# Aquarium_Schematic.net
KiCad netlist of a schematic drawn in EasyEDA
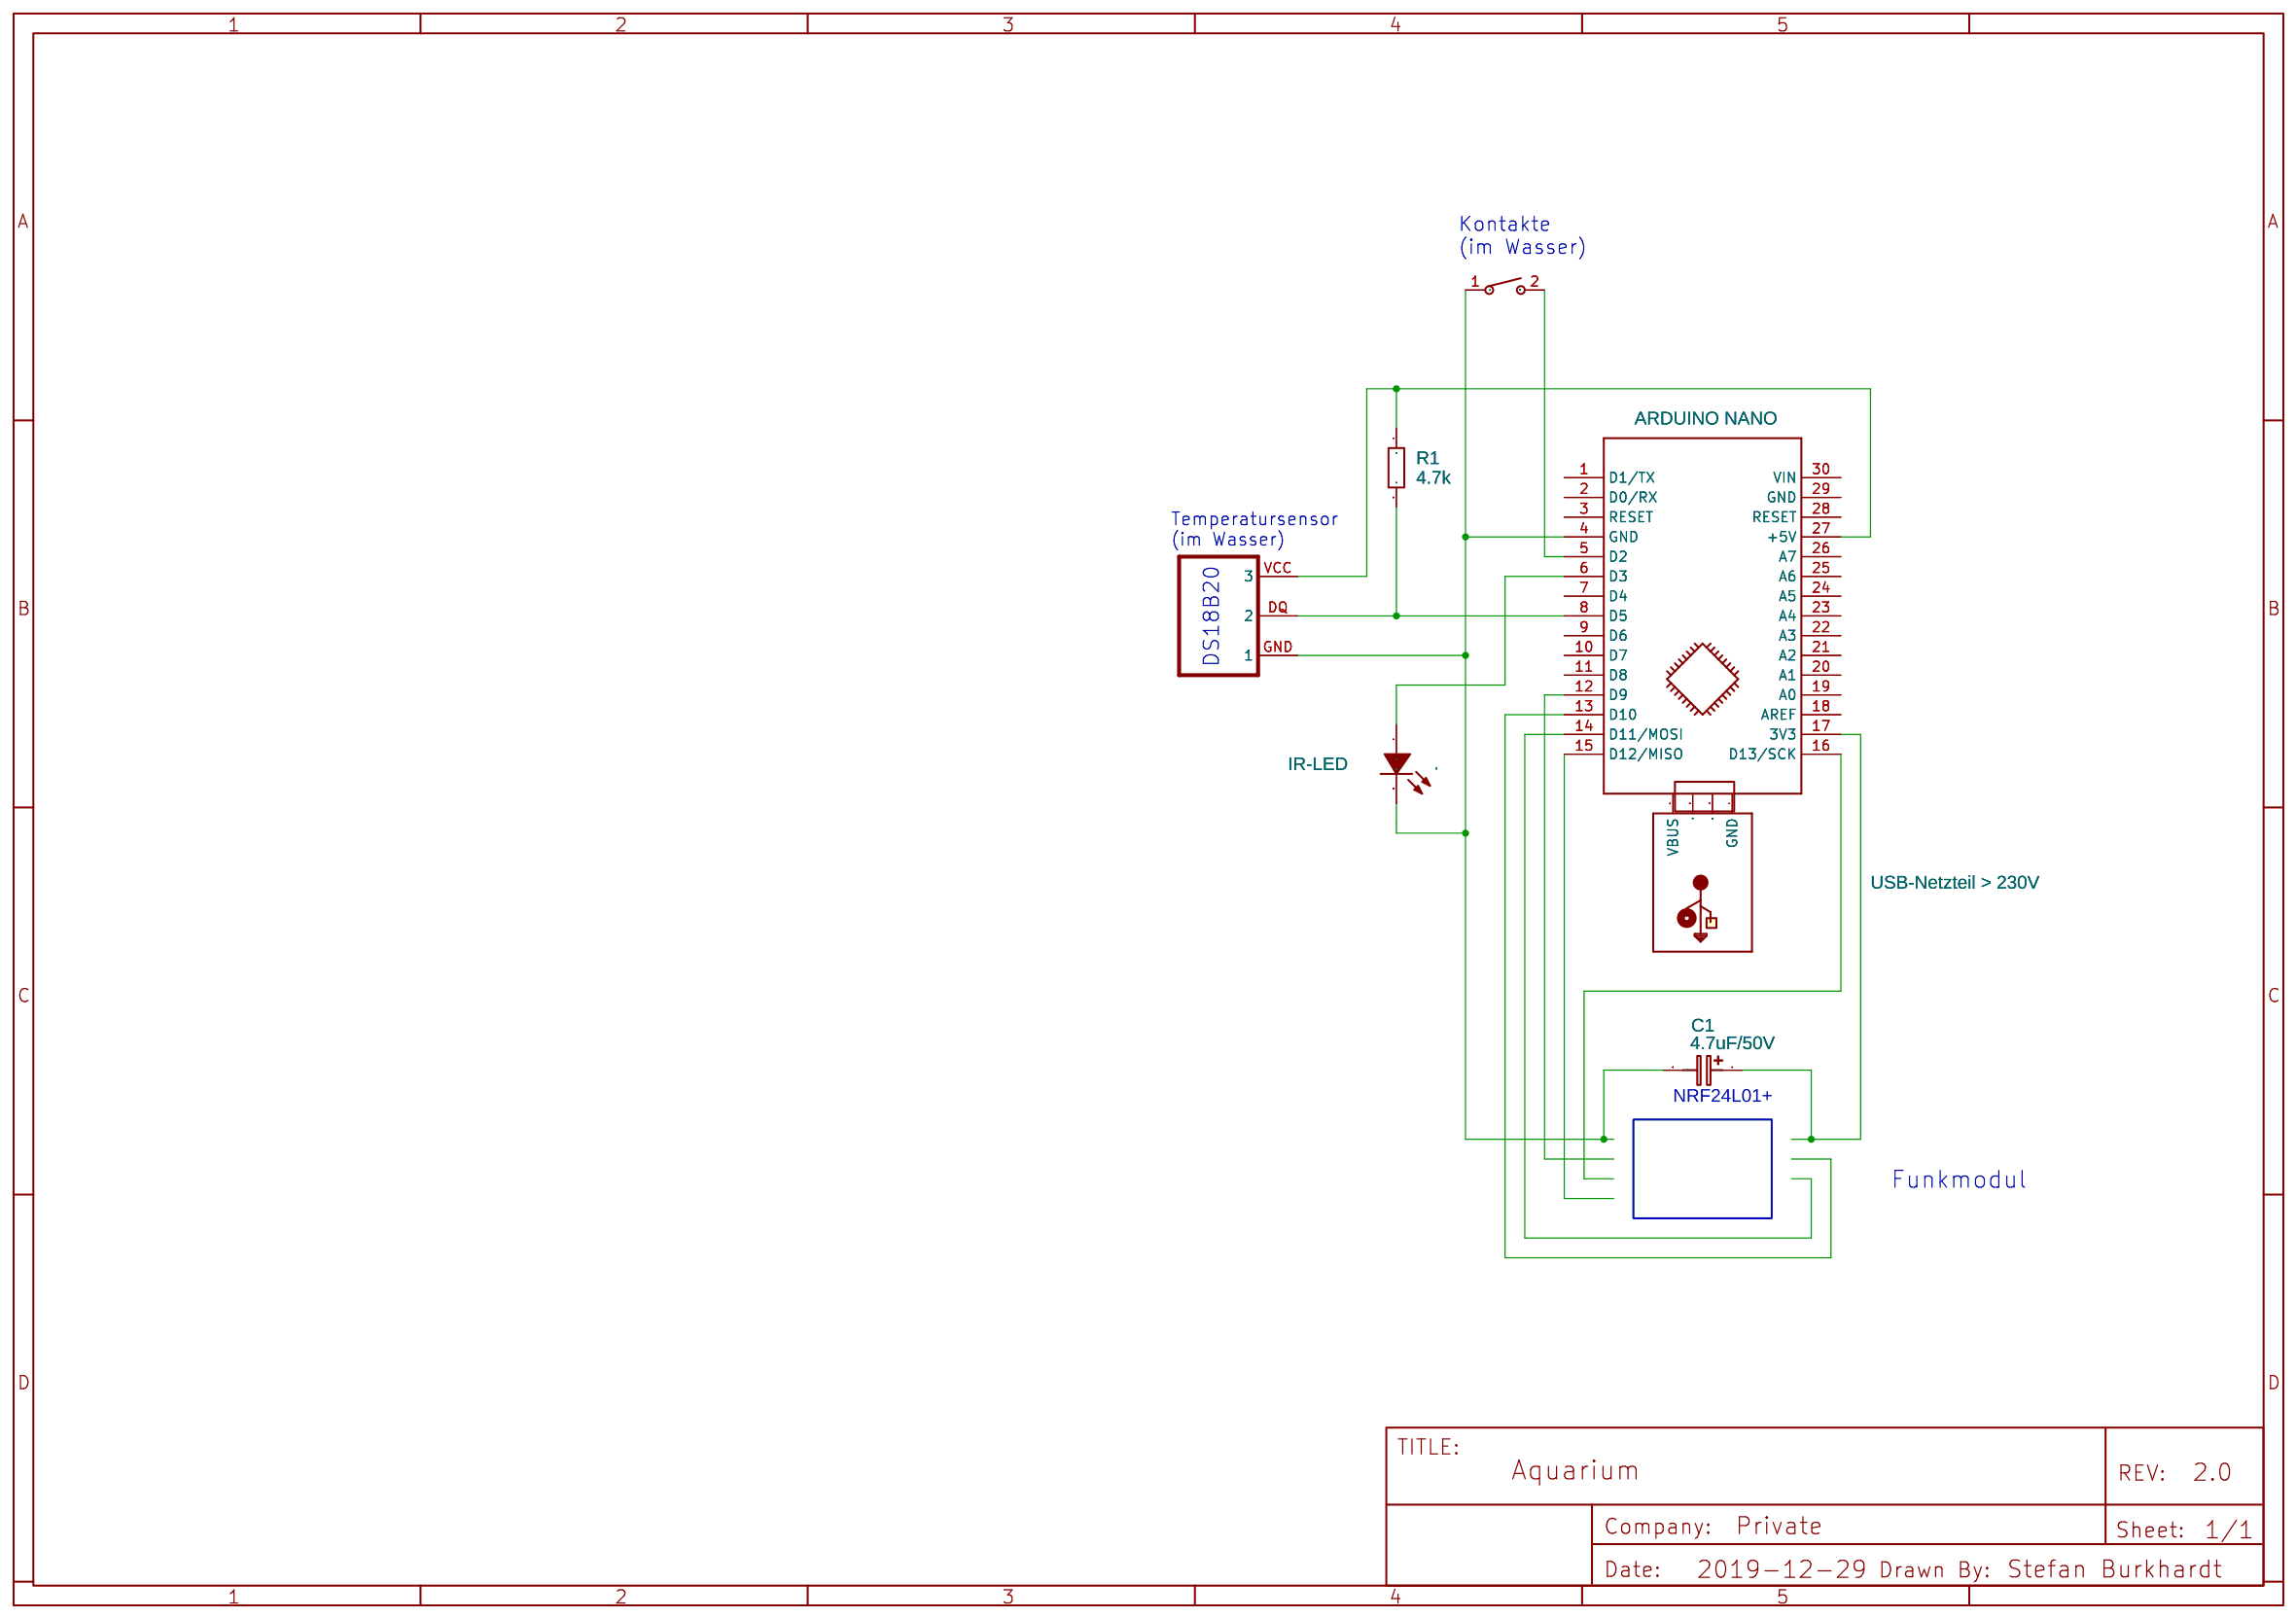
[diagram p0: schematic sheet]

(export (version "E")
  (design (tool "Eeschema 10.0.6"))
  (components
    (comp (ref ".")
      (value "IR-LED")
      (fields (field (name "BOM_Manufacturer Part") "?"))
      (libsource (lib "") (part "Unknown_574_403"))
    )
    (comp (ref "C1")
      (value "4.7uF/50V")
      (fields (field (name "BOM_Manufacturer Part") "?"))
      (libsource (lib "") (part "Cap_Electrolytic(TH)_D3.0XF1.5_EU"))
    )
    (comp (ref "R1")
      (value "4.7k")
      (fields (field (name "BOM_Manufacturer Part") "?"))
      (libsource (lib "") (part "Res_AXIAL-0.3(1/8W)_EU"))
    )
    (comp (ref "SW1")
      (value "Wasser-Kurzschluss")
      (fields
        (field (name "BOM_Manufacturer Part") "K2-1107ST-A4SW-06")
        (field (name "BOM_Supplier Part") "C118141")
      )
      (libsource (lib "") (part "Unknown_755_140"))
    )
    (comp (ref "U1")
      (value "ARDUINO NANO")
      (fields (field (name "BOM_Manufacturer Part") "?"))
      (libsource (lib "") (part "Unknown_855_310"))
    )
    (comp (ref "U2")
      (value "DS18B20")
      (fields (field (name "BOM_Manufacturer Part") "?"))
      (libsource (lib "") (part "Unknown_650_325"))
    )
    (comp (ref "X1")
      (value "USB-Netzteil > 230V")
      (fields (field (name "BOM_Manufacturer Part") "?"))
      (libsource (lib "") (part "Unknown_855_435"))
    )
  )
  (nets
    (net (code "1") (name "Net-(.-A)") (class "Default")
      (node (ref ".") (pin "1") (pinfunction "A_1") (pintype "unspecified"))
      (node (ref "U1") (pin "6") (pinfunction "D3_6") (pintype "unspecified"))
    )
    (net (code "2") (name "Net-(.-K)") (class "Default")
      (node (ref ".") (pin "2") (pinfunction "K_2") (pintype "unspecified"))
      (node (ref "C1") (pin "2") (pinfunction "2_2") (pintype "unspecified"))
      (node (ref "SW1") (pin "1") (pinfunction "1_1") (pintype "unspecified"))
      (node (ref "U1") (pin "4") (pinfunction "GND_4") (pintype "unspecified"))
      (node (ref "U2") (pin "GND") (pinfunction "1_GND") (pintype "unspecified"))
    )
    (net (code "3") (name "Net-(U1-+5V)") (class "Default")
      (node (ref "R1") (pin "1") (pinfunction "1_1") (pintype "unspecified"))
      (node (ref "U1") (pin "27") (pinfunction "+5V_27") (pintype "unspecified"))
      (node (ref "U2") (pin "VCC") (pinfunction "3_VCC") (pintype "unspecified"))
    )
    (net (code "4") (name "Net-(U1-3V3)") (class "Default")
      (node (ref "C1") (pin "1") (pinfunction "1_1") (pintype "unspecified"))
      (node (ref "U1") (pin "17") (pinfunction "3V3_17") (pintype "unspecified"))
    )
    (net (code "5") (name "Net-(U1-D2)") (class "Default")
      (node (ref "SW1") (pin "2") (pinfunction "2_2") (pintype "unspecified"))
      (node (ref "U1") (pin "5") (pinfunction "D2_5") (pintype "unspecified"))
    )
    (net (code "6") (name "Net-(U1-D5)") (class "Default")
      (node (ref "R1") (pin "2") (pinfunction "2_2") (pintype "unspecified"))
      (node (ref "U1") (pin "8") (pinfunction "D5_8") (pintype "unspecified"))
      (node (ref "U2") (pin "DQ") (pinfunction "2_DQ") (pintype "unspecified"))
    )
    (net (code "7") (name "unconnected-(U1-A0-Pad19)") (class "Default")
      (node (ref "U1") (pin "19") (pinfunction "A0_19") (pintype "unspecified"))
    )
    (net (code "8") (name "unconnected-(U1-A1-Pad20)") (class "Default")
      (node (ref "U1") (pin "20") (pinfunction "A1_20") (pintype "unspecified"))
    )
    (net (code "9") (name "unconnected-(U1-A2-Pad21)") (class "Default")
      (node (ref "U1") (pin "21") (pinfunction "A2_21") (pintype "unspecified"))
    )
    (net (code "10") (name "unconnected-(U1-A3-Pad22)") (class "Default")
      (node (ref "U1") (pin "22") (pinfunction "A3_22") (pintype "unspecified"))
    )
    (net (code "11") (name "unconnected-(U1-A4-Pad23)") (class "Default")
      (node (ref "U1") (pin "23") (pinfunction "A4_23") (pintype "unspecified"))
    )
    (net (code "12") (name "unconnected-(U1-A5-Pad24)") (class "Default")
      (node (ref "U1") (pin "24") (pinfunction "A5_24") (pintype "unspecified"))
    )
    (net (code "13") (name "unconnected-(U1-A6-Pad25)") (class "Default")
      (node (ref "U1") (pin "25") (pinfunction "A6_25") (pintype "unspecified"))
    )
    (net (code "14") (name "unconnected-(U1-A7-Pad26)") (class "Default")
      (node (ref "U1") (pin "26") (pinfunction "A7_26") (pintype "unspecified"))
    )
    (net (code "15") (name "unconnected-(U1-AREF-Pad18)") (class "Default")
      (node (ref "U1") (pin "18") (pinfunction "AREF_18") (pintype "unspecified"))
    )
    (net (code "16") (name "unconnected-(U1-D0{slash}RX-Pad2)") (class "Default")
      (node (ref "U1") (pin "2") (pinfunction "D0/RX_2") (pintype "unspecified"))
    )
    (net (code "17") (name "unconnected-(U1-D1{slash}TX-Pad1)") (class "Default")
      (node (ref "U1") (pin "1") (pinfunction "D1/TX_1") (pintype "unspecified"))
    )
    (net (code "18") (name "unconnected-(U1-D4-Pad7)") (class "Default")
      (node (ref "U1") (pin "7") (pinfunction "D4_7") (pintype "unspecified"))
    )
    (net (code "19") (name "unconnected-(U1-D6-Pad9)") (class "Default")
      (node (ref "U1") (pin "9") (pinfunction "D6_9") (pintype "unspecified"))
    )
    (net (code "20") (name "unconnected-(U1-D7-Pad10)") (class "Default")
      (node (ref "U1") (pin "10") (pinfunction "D7_10") (pintype "unspecified"))
    )
    (net (code "21") (name "unconnected-(U1-D8-Pad11)") (class "Default")
      (node (ref "U1") (pin "11") (pinfunction "D8_11") (pintype "unspecified"))
    )
    (net (code "22") (name "unconnected-(U1-D9-Pad12)") (class "Default")
      (node (ref "U1") (pin "12") (pinfunction "D9_12") (pintype "unspecified"))
    )
    (net (code "23") (name "unconnected-(U1-D10-Pad13)") (class "Default")
      (node (ref "U1") (pin "13") (pinfunction "D10_13") (pintype "unspecified"))
    )
    (net (code "24") (name "unconnected-(U1-D11{slash}MOSI-Pad14)") (class "Default")
      (node (ref "U1") (pin "14") (pinfunction "D11/MOSI_14") (pintype "unspecified"))
    )
    (net (code "25") (name "unconnected-(U1-D12{slash}MISO-Pad15)") (class "Default")
      (node (ref "U1") (pin "15") (pinfunction "D12/MISO_15") (pintype "unspecified"))
    )
    (net (code "26") (name "unconnected-(U1-D13{slash}SCK-Pad16)") (class "Default")
      (node (ref "U1") (pin "16") (pinfunction "D13/SCK_16") (pintype "unspecified"))
    )
    (net (code "27") (name "unconnected-(U1-GND-Pad29)") (class "Default")
      (node (ref "U1") (pin "29") (pinfunction "GND_29") (pintype "unspecified"))
    )
    (net (code "28") (name "unconnected-(U1-RESET-Pad3)") (class "Default")
      (node (ref "U1") (pin "3") (pinfunction "RESET_3") (pintype "unspecified"))
    )
    (net (code "29") (name "unconnected-(U1-RESET-Pad28)") (class "Default")
      (node (ref "U1") (pin "28") (pinfunction "RESET_28") (pintype "unspecified"))
    )
    (net (code "30") (name "unconnected-(U1-VIN-Pad30)") (class "Default")
      (node (ref "U1") (pin "30") (pinfunction "VIN_30") (pintype "unspecified"))
    )
    (net (code "31") (name "unconnected-(X1-D+-Pad3)") (class "Default")
      (node (ref "X1") (pin "3") (pinfunction "D+_3") (pintype "unspecified"))
    )
    (net (code "32") (name "unconnected-(X1-D--Pad2)") (class "Default")
      (node (ref "X1") (pin "2") (pinfunction "D-_2") (pintype "unspecified"))
    )
    (net (code "33") (name "unconnected-(X1-GND-Pad4)") (class "Default")
      (node (ref "X1") (pin "4") (pinfunction "GND_4") (pintype "passive"))
    )
    (net (code "34") (name "unconnected-(X1-VBUS-Pad1)") (class "Default")
      (node (ref "X1") (pin "1") (pinfunction "VBUS_1") (pintype "passive"))
    )
  )
)
